# EasyEDA-Schematic.net
KiCad netlist of a schematic drawn in EasyEDA
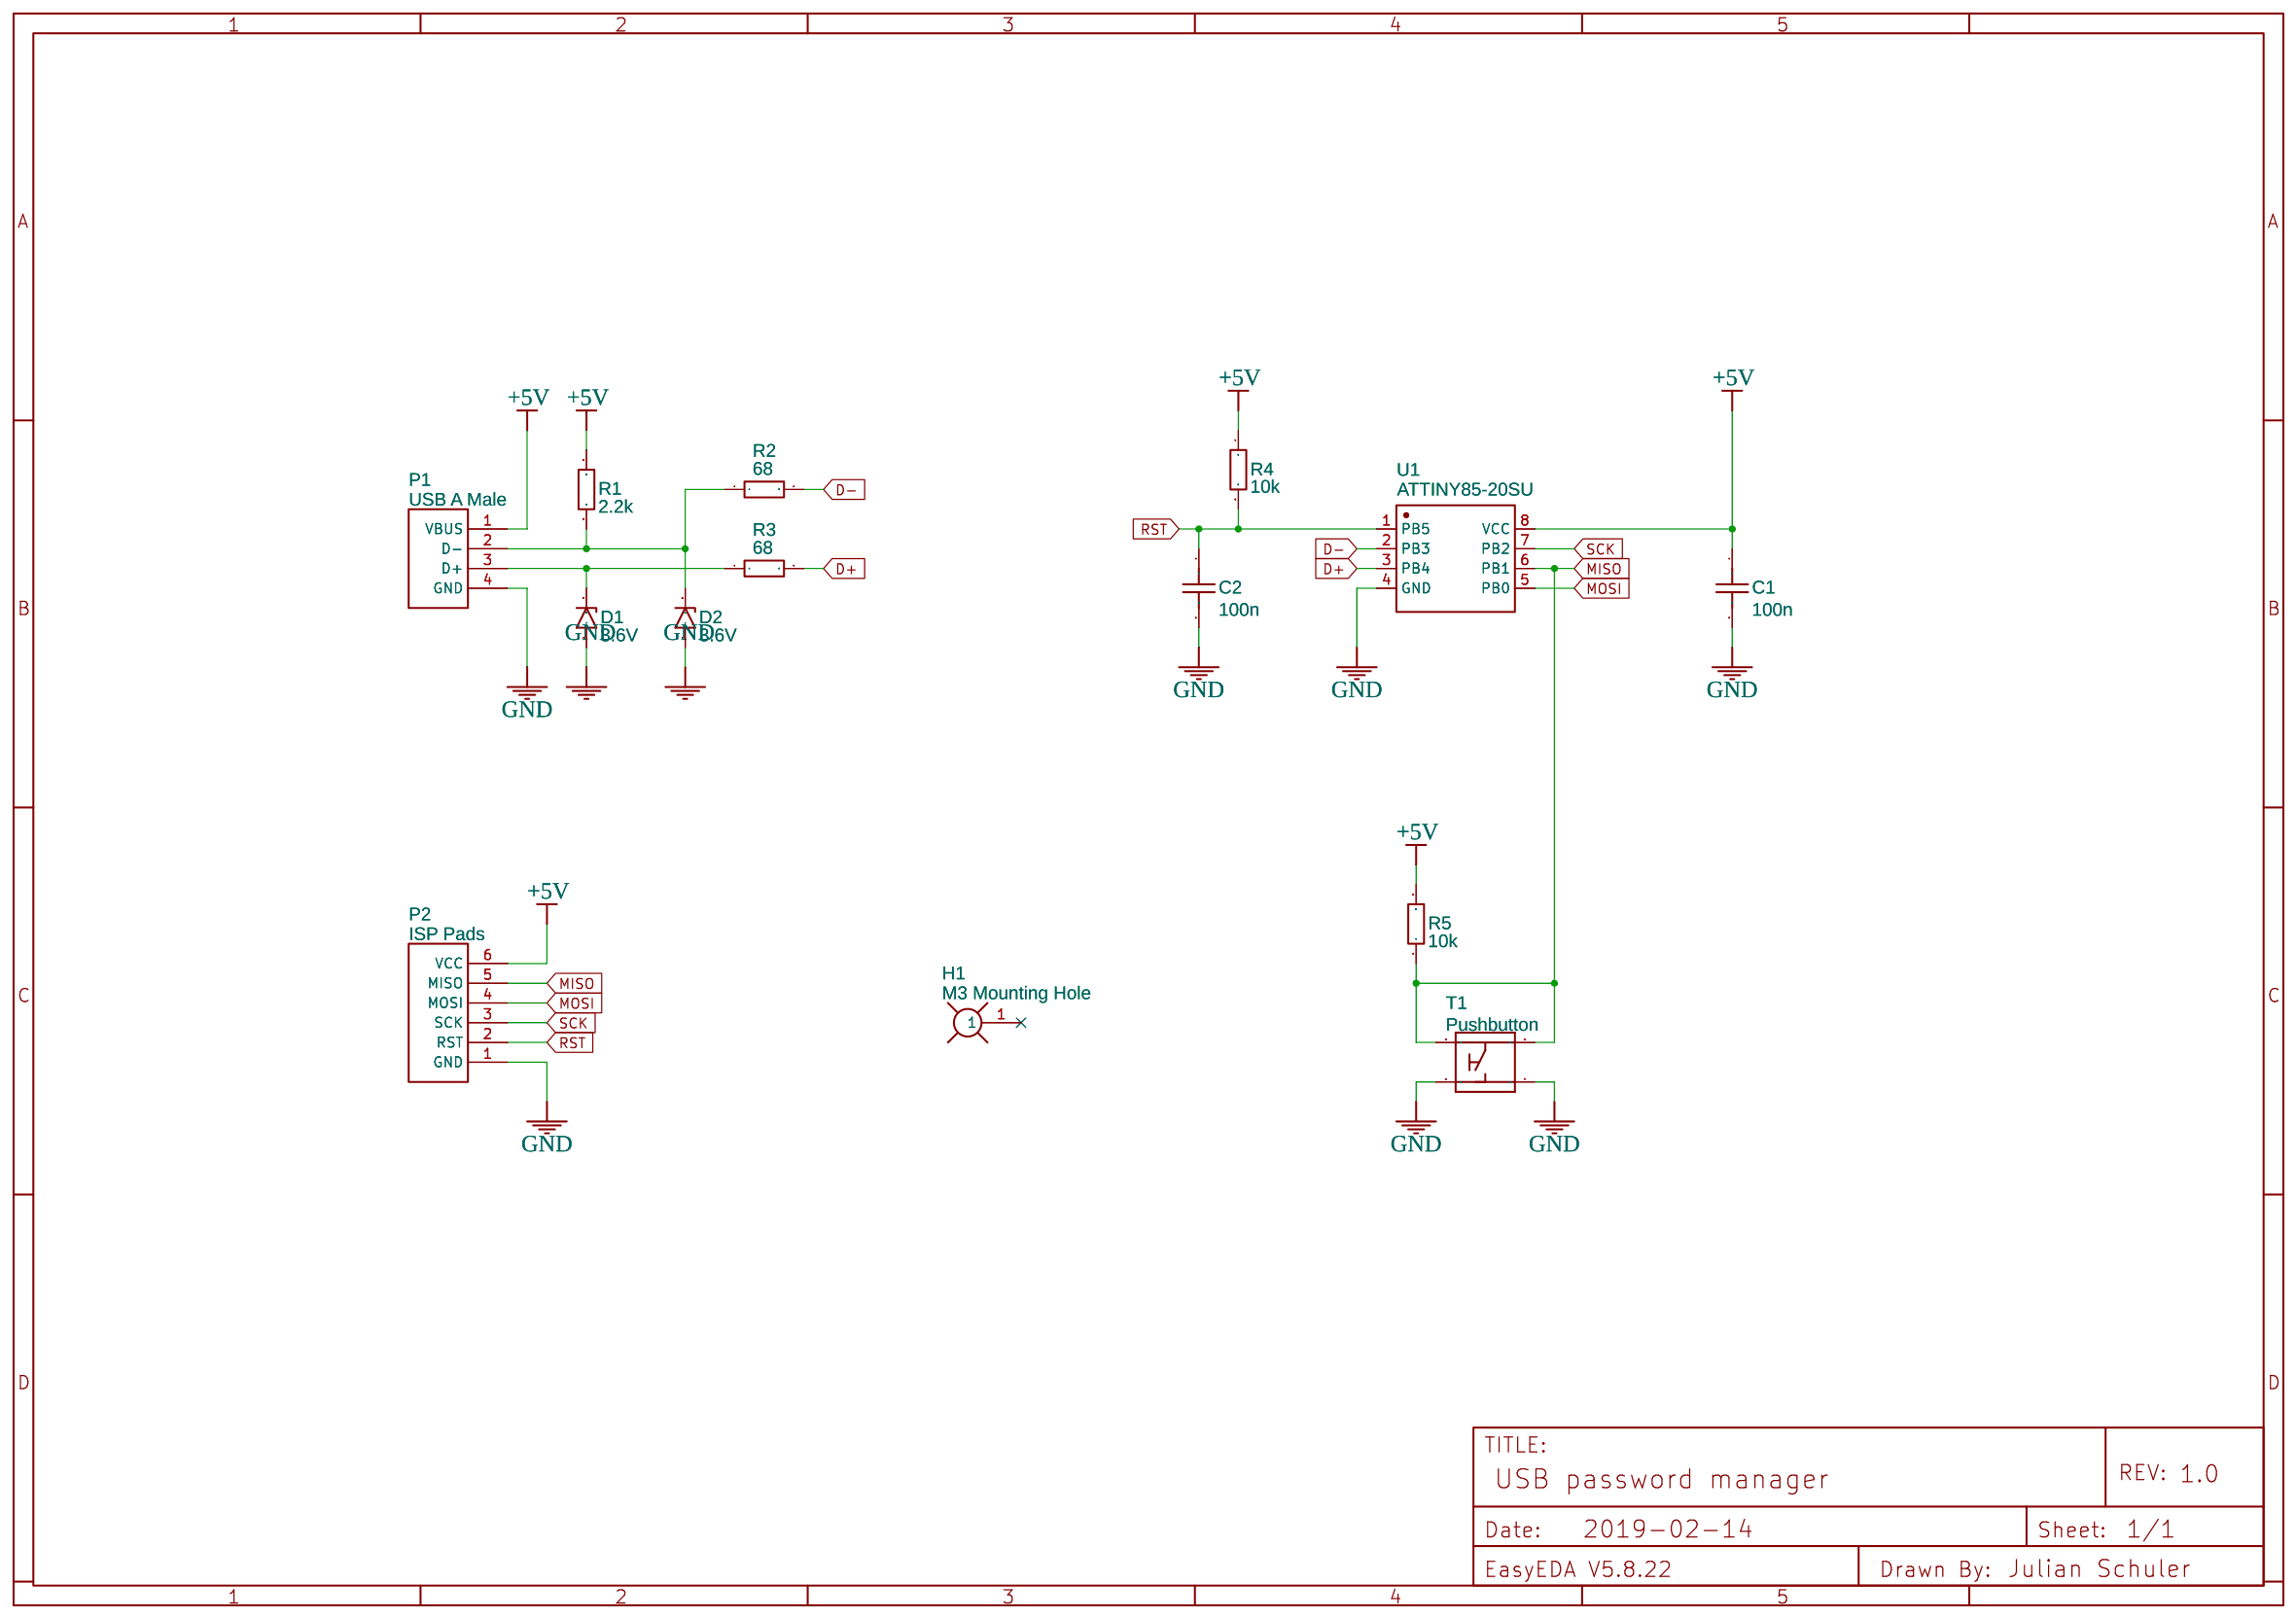
[diagram p0: schematic sheet]

(export (version "E")
  (design (tool "Eeschema 10.0.6"))
  (components
    (comp (ref "C1")
      (value "100n")
      (fields (field (name "BOM_Manufacturer Part") "?"))
      (libsource (lib "") (part "Cap_0603_US"))
    )
    (comp (ref "C2")
      (value "100n")
      (fields (field (name "BOM_Manufacturer Part") "?"))
      (libsource (lib "") (part "Cap_0603_US"))
    )
    (comp (ref "D1")
      (value "3.6V")
      (fields (field (name "BOM_Manufacturer Part") "?"))
      (libsource (lib "") (part "Unknown_290_300"))
    )
    (comp (ref "D2")
      (value "3.6V")
      (fields (field (name "BOM_Manufacturer Part") "?"))
      (libsource (lib "") (part "Unknown_340_300"))
    )
    (comp (ref "H1")
      (value "M3 Mounting Hole")
      (fields (field (name "BOM_Manufacturer Part") "?"))
      (libsource (lib "") (part "Unknown_480_510"))
    )
    (comp (ref "P1")
      (value "USB A Male")
      (fields (field (name "BOM_Manufacturer Part") "?"))
      (libsource (lib "") (part "Unknown_230_290"))
    )
    (comp (ref "P2") (value "ISP Pads") (libsource (lib "") (part "Unknown_230_530")))
    (comp (ref "R1")
      (value "2.2k")
      (fields (field (name "BOM_Manufacturer Part") "?"))
      (libsource (lib "") (part "Res_0603(1/10W)_EU"))
    )
    (comp (ref "R2")
      (value "68")
      (fields (field (name "BOM_Manufacturer Part") "?"))
      (libsource (lib "") (part "Res_0603(1/10W)_EU_2"))
    )
    (comp (ref "R3")
      (value "68")
      (fields (field (name "BOM_Manufacturer Part") "?"))
      (libsource (lib "") (part "Res_0603(1/10W)_EU_2"))
    )
    (comp (ref "R4")
      (value "10k")
      (fields (field (name "BOM_Manufacturer Part") "?"))
      (libsource (lib "") (part "Res_0603(1/10W)_EU_1"))
    )
    (comp (ref "R5")
      (value "10k")
      (fields (field (name "BOM_Manufacturer Part") "?"))
      (libsource (lib "") (part "Res_0603(1/10W)_EU"))
    )
    (comp (ref "T1")
      (value "Pushbutton")
      (fields (field (name "BOM_Manufacturer Part") "TS-1109"))
      (libsource (lib "") (part "Unknown_750_530"))
    )
    (comp (ref "U1")
      (value "ATTINY85-20SU")
      (fields (field (name "BOM_Supplier Part") "C89852"))
      (libsource (lib "") (part "Unknown_730_280"))
    )
  )
  (nets
    (net (code "1") (name "+5V") (class "Default")
      (node (ref "C1") (pin "1") (pinfunction "1_1") (pintype "unspecified"))
      (node (ref "P1") (pin "1") (pinfunction "VBUS_1") (pintype "unspecified"))
      (node (ref "P2") (pin "6") (pinfunction "VCC_6") (pintype "unspecified"))
      (node (ref "R1") (pin "2") (pinfunction "2_2") (pintype "unspecified"))
      (node (ref "R4") (pin "1") (pinfunction "1_1") (pintype "unspecified"))
      (node (ref "R5") (pin "2") (pinfunction "2_2") (pintype "unspecified"))
      (node (ref "U1") (pin "8") (pinfunction "VCC_8") (pintype "unspecified"))
    )
    (net (code "2") (name "D+") (class "Default")
      (node (ref "R3") (pin "2") (pinfunction "2_2") (pintype "unspecified"))
      (node (ref "U1") (pin "3") (pinfunction "PB4_3") (pintype "unspecified"))
    )
    (net (code "3") (name "D-") (class "Default")
      (node (ref "R2") (pin "2") (pinfunction "2_2") (pintype "unspecified"))
      (node (ref "U1") (pin "2") (pinfunction "PB3_2") (pintype "unspecified"))
    )
    (net (code "4") (name "GND") (class "Default")
      (node (ref "C1") (pin "2") (pinfunction "2_2") (pintype "unspecified"))
      (node (ref "C2") (pin "2") (pinfunction "2_2") (pintype "unspecified"))
      (node (ref "D1") (pin "A") (pinfunction "A_A") (pintype "unspecified"))
      (node (ref "D2") (pin "A") (pinfunction "A_A") (pintype "unspecified"))
      (node (ref "P1") (pin "4") (pinfunction "GND_4") (pintype "unspecified"))
      (node (ref "P2") (pin "1") (pinfunction "GND_1") (pintype "unspecified"))
      (node (ref "T1") (pin "3") (pinfunction "B0_3") (pintype "unspecified"))
      (node (ref "T1") (pin "4") (pinfunction "B1_4") (pintype "unspecified"))
      (node (ref "U1") (pin "4") (pinfunction "GND_4") (pintype "unspecified"))
    )
    (net (code "5") (name "MISO") (class "Default")
      (node (ref "P2") (pin "5") (pinfunction "MISO_5") (pintype "unspecified"))
      (node (ref "R5") (pin "1") (pinfunction "1_1") (pintype "unspecified"))
      (node (ref "T1") (pin "1") (pinfunction "A1_1") (pintype "unspecified"))
      (node (ref "T1") (pin "2") (pinfunction "A0_2") (pintype "unspecified"))
      (node (ref "U1") (pin "6") (pinfunction "PB1_6") (pintype "unspecified"))
    )
    (net (code "6") (name "MOSI") (class "Default")
      (node (ref "P2") (pin "4") (pinfunction "MOSI_4") (pintype "unspecified"))
      (node (ref "U1") (pin "5") (pinfunction "PB0_5") (pintype "unspecified"))
    )
    (net (code "7") (name "Net-(P1-D+)") (class "Default")
      (node (ref "D1") (pin "C") (pinfunction "C_C") (pintype "unspecified"))
      (node (ref "P1") (pin "3") (pinfunction "D+_3") (pintype "unspecified"))
      (node (ref "R3") (pin "1") (pinfunction "1_1") (pintype "unspecified"))
    )
    (net (code "8") (name "Net-(P1-D-)") (class "Default")
      (node (ref "D2") (pin "C") (pinfunction "C_C") (pintype "unspecified"))
      (node (ref "P1") (pin "2") (pinfunction "D-_2") (pintype "unspecified"))
      (node (ref "R1") (pin "1") (pinfunction "1_1") (pintype "unspecified"))
      (node (ref "R2") (pin "1") (pinfunction "1_1") (pintype "unspecified"))
    )
    (net (code "9") (name "RST") (class "Default")
      (node (ref "C2") (pin "1") (pinfunction "1_1") (pintype "unspecified"))
      (node (ref "P2") (pin "2") (pinfunction "RST_2") (pintype "unspecified"))
      (node (ref "R4") (pin "2") (pinfunction "2_2") (pintype "unspecified"))
      (node (ref "U1") (pin "1") (pinfunction "PB5_1") (pintype "unspecified"))
    )
    (net (code "10") (name "SCK") (class "Default")
      (node (ref "P2") (pin "3") (pinfunction "SCK_3") (pintype "unspecified"))
      (node (ref "U1") (pin "7") (pinfunction "PB2_7") (pintype "unspecified"))
    )
    (net (code "11") (name "unconnected-(H1-Pad1)") (class "Default")
      (node (ref "H1") (pin "1") (pinfunction "1_1") (pintype "unspecified+no_connect"))
    )
  )
)
